# ProPrj_Videocraft_USB_Hub_2026-04-26.net
KiCad netlist of a schematic drawn in EasyEDA Pro
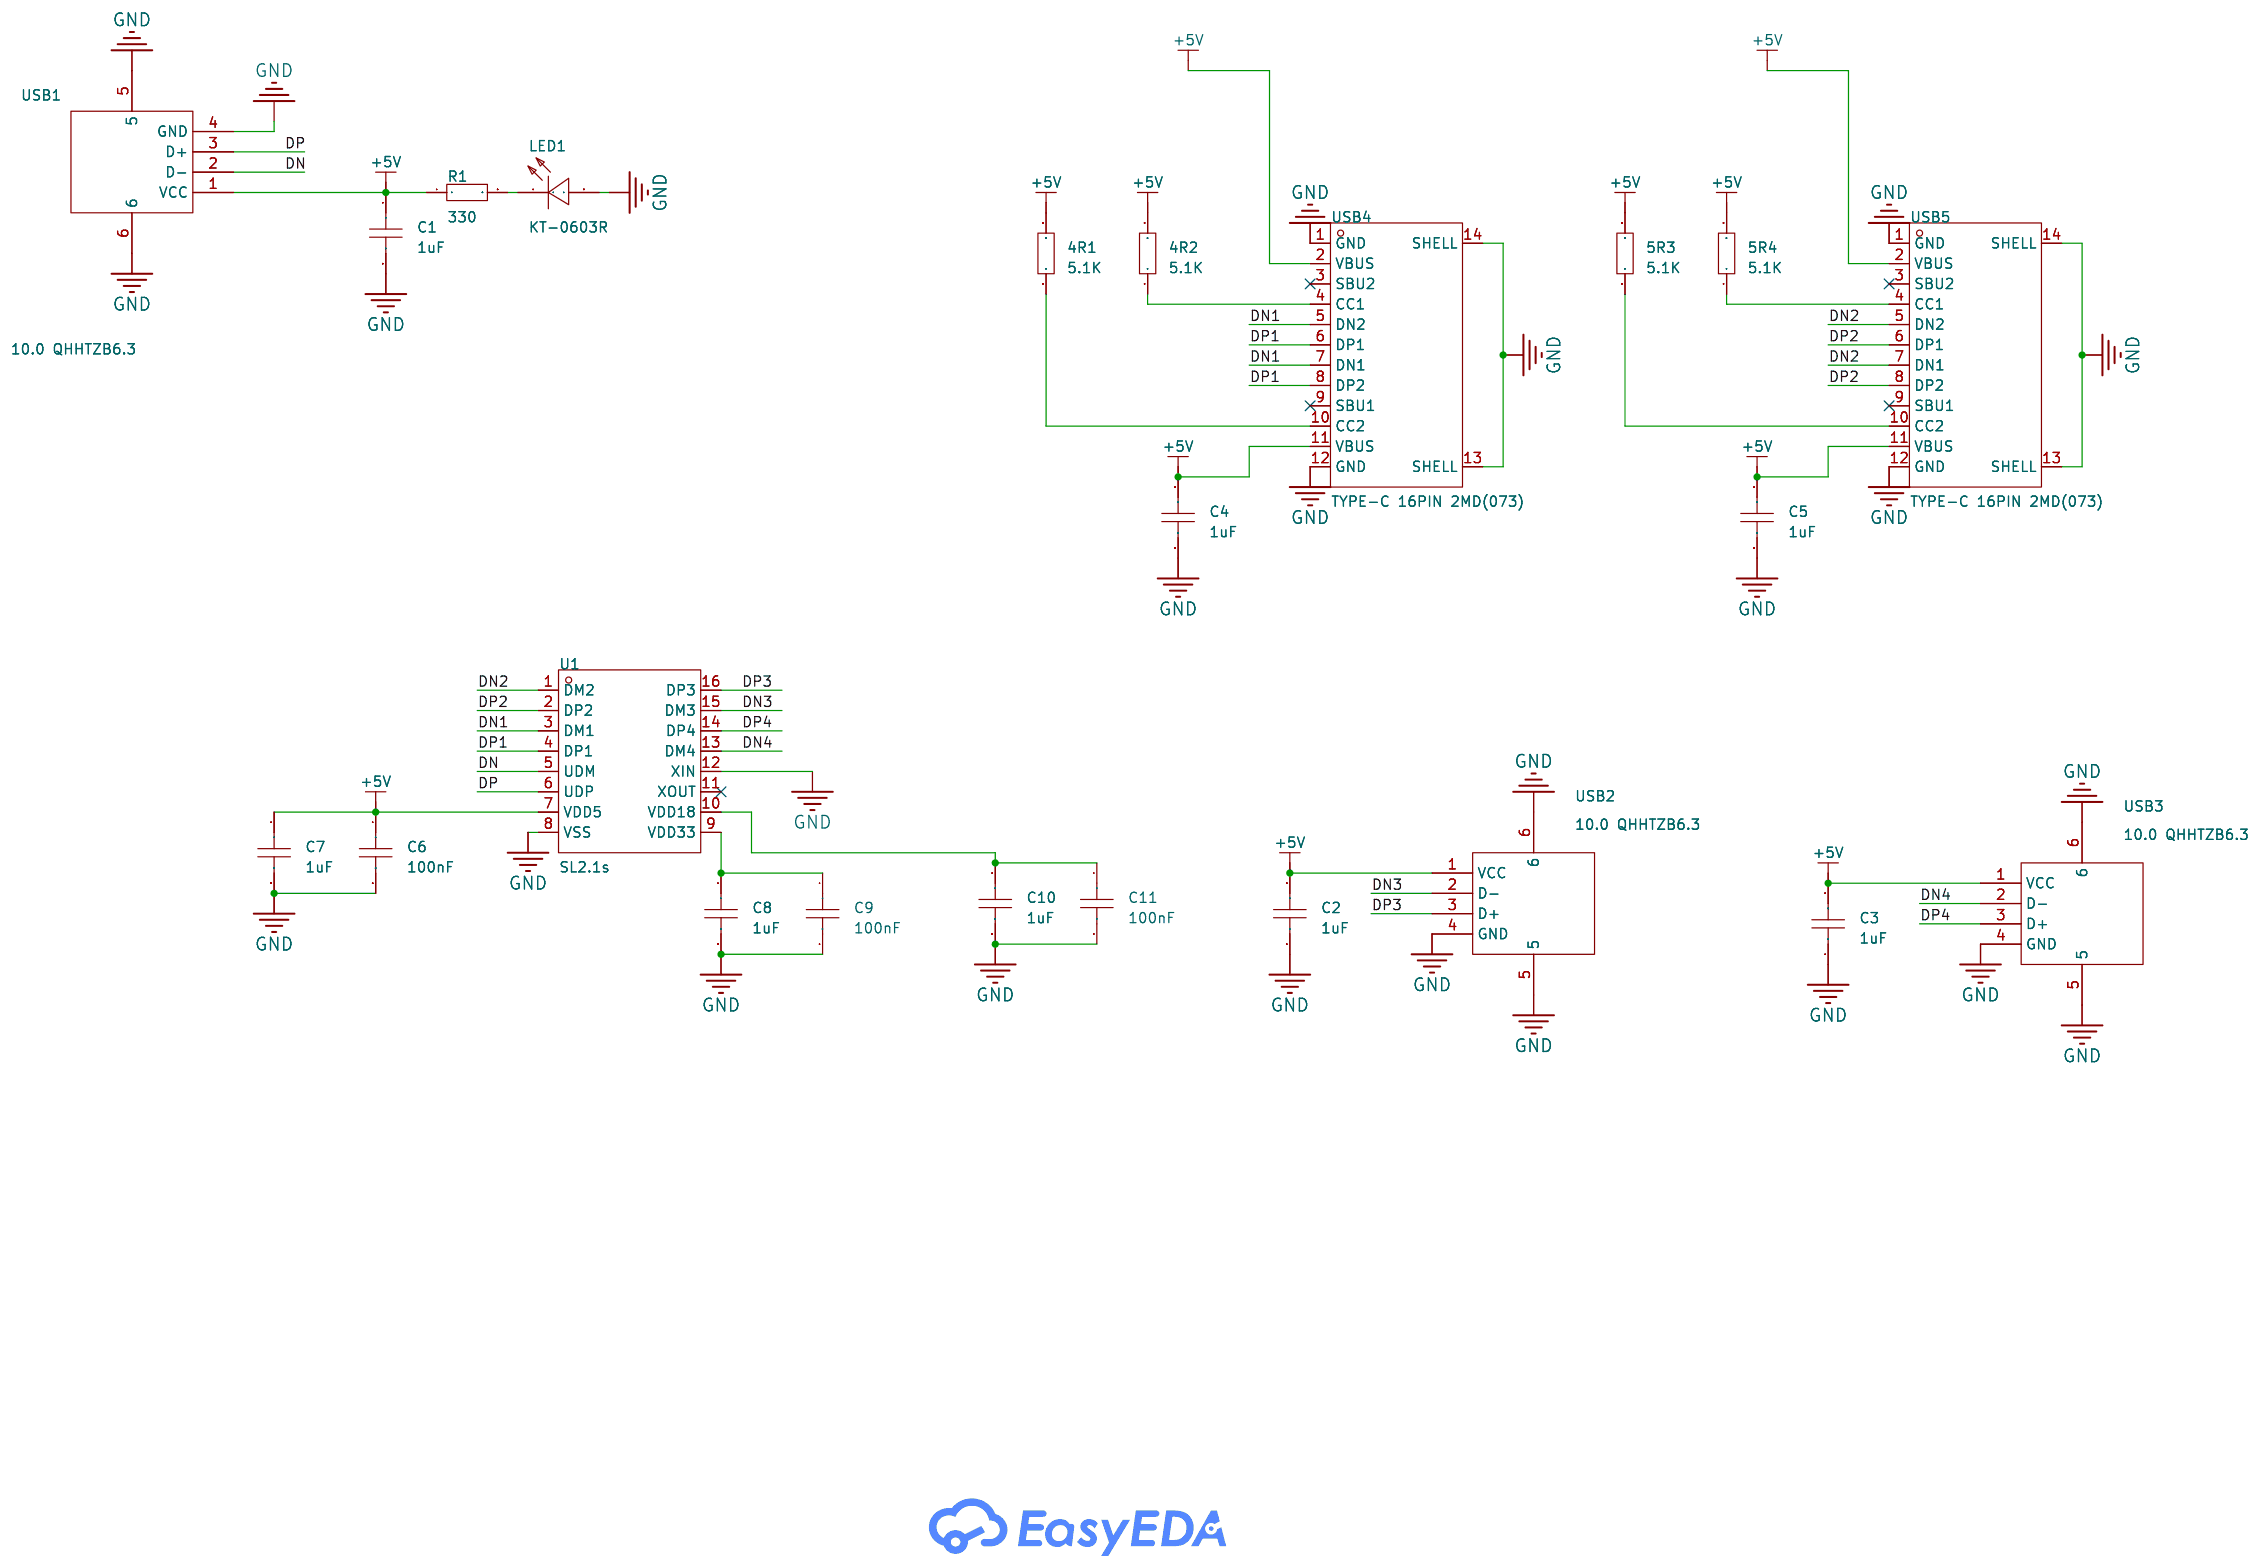
[diagram p0: schematic sheet]

(export (version "E")
  (design (tool "Eeschema 10.0.6"))
  (components
    (comp (ref "4R1")
      (value "5.1K")
      (footprint "easyedapro:R0603")
      (libsource (lib "easyedapro") (part "Res"))
    )
    (comp (ref "4R2")
      (value "5.1K")
      (footprint "easyedapro:R0603")
      (libsource (lib "easyedapro") (part "Res"))
    )
    (comp (ref "5R3")
      (value "5.1K")
      (footprint "easyedapro:R0603")
      (libsource (lib "easyedapro") (part "Res"))
    )
    (comp (ref "5R4")
      (value "5.1K")
      (footprint "easyedapro:R0603")
      (libsource (lib "easyedapro") (part "Res"))
    )
    (comp (ref "C1") (value "1uF") (footprint "easyedapro:C0603") (libsource (lib "easyedapro") (part "CAP")))
    (comp (ref "C2") (value "1uF") (footprint "easyedapro:C0603") (libsource (lib "easyedapro") (part "CAP")))
    (comp (ref "C3") (value "1uF") (footprint "easyedapro:C0603") (libsource (lib "easyedapro") (part "CAP")))
    (comp (ref "C4") (value "1uF") (footprint "easyedapro:C0603") (libsource (lib "easyedapro") (part "CAP")))
    (comp (ref "C5") (value "1uF") (footprint "easyedapro:C0603") (libsource (lib "easyedapro") (part "CAP")))
    (comp (ref "C6")
      (value "100nF")
      (footprint "easyedapro:C0603")
      (libsource (lib "easyedapro") (part "CAP"))
    )
    (comp (ref "C7") (value "1uF") (footprint "easyedapro:C0603") (libsource (lib "easyedapro") (part "CAP")))
    (comp (ref "C8") (value "1uF") (footprint "easyedapro:C0603") (libsource (lib "easyedapro") (part "CAP")))
    (comp (ref "C9")
      (value "100nF")
      (footprint "easyedapro:C0603")
      (libsource (lib "easyedapro") (part "CAP"))
    )
    (comp (ref "C10")
      (value "1uF")
      (footprint "easyedapro:C0603")
      (libsource (lib "easyedapro") (part "CAP"))
    )
    (comp (ref "C11")
      (value "100nF")
      (footprint "easyedapro:C0603")
      (libsource (lib "easyedapro") (part "CAP"))
    )
    (comp (ref "LED1")
      (value "KT-0603R")
      (footprint "easyedapro:LED0603-RD")
      (fields (field (name "Manufacturer") "KENTO"))
      (libsource (lib "easyedapro") (part "KT-0603R"))
    )
    (comp (ref "R1") (value "330") (footprint "easyedapro:R0603") (libsource (lib "easyedapro") (part "Res")))
    (comp (ref "U1")
      (value "SL2.1s")
      (footprint "easyedapro:SSOP-16_L4.6-W2.6-P0.53-LS4.0-BL")
      (fields (field (name "Manufacturer") "CoreChips(和芯润德)"))
      (libsource (lib "easyedapro") (part "SL2.1S"))
    )
    (comp (ref "USB1")
      (value "10.0 QHHTZB6.3")
      (footprint "easyedapro:USB-A-TH_10.0QHHTZB6.3")
      (fields (field (name "Manufacturer") "SHOU HAN(首韩)"))
      (libsource (lib "easyedapro") (part "10.0 QHHTZB6.3"))
    )
    (comp (ref "USB2")
      (value "10.0 QHHTZB6.3")
      (footprint "easyedapro:USB-A-TH_10.0QHHTZB6.3")
      (fields (field (name "Manufacturer") "SHOU HAN(首韩)"))
      (libsource (lib "easyedapro") (part "10.0 QHHTZB6.3"))
    )
    (comp (ref "USB3")
      (value "10.0 QHHTZB6.3")
      (footprint "easyedapro:USB-A-TH_10.0QHHTZB6.3")
      (fields (field (name "Manufacturer") "SHOU HAN(首韩)"))
      (libsource (lib "easyedapro") (part "10.0 QHHTZB6.3"))
    )
    (comp (ref "USB4")
      (value "TYPE-C 16PIN 2MD(073)")
      (footprint "easyedapro:USB-C-SMD_TYPE-C-6PIN-2MD-073")
      (fields (field (name "Manufacturer") "SHOU HAN(首韩)"))
      (libsource (lib "easyedapro") (part "TYPE-C 16PIN 2MD(073)"))
    )
    (comp (ref "USB5")
      (value "TYPE-C 16PIN 2MD(073)")
      (footprint "easyedapro:USB-C-SMD_TYPE-C-6PIN-2MD-073")
      (fields (field (name "Manufacturer") "SHOU HAN(首韩)"))
      (libsource (lib "easyedapro") (part "TYPE-C 16PIN 2MD(073)"))
    )
  )
  (nets
    (net (code "1") (name "+5V") (class "Default")
      (node (ref "4R1") (pin "2") (pinfunction "2_2") (pintype "input"))
      (node (ref "4R2") (pin "2") (pinfunction "2_2") (pintype "input"))
      (node (ref "5R3") (pin "2") (pinfunction "2_2") (pintype "input"))
      (node (ref "5R4") (pin "2") (pinfunction "2_2") (pintype "input"))
      (node (ref "C1") (pin "1") (pinfunction "1_1") (pintype "input"))
      (node (ref "C2") (pin "2") (pinfunction "2_2") (pintype "input"))
      (node (ref "C3") (pin "2") (pinfunction "2_2") (pintype "input"))
      (node (ref "C4") (pin "1") (pinfunction "1_1") (pintype "input"))
      (node (ref "C5") (pin "1") (pinfunction "1_1") (pintype "input"))
      (node (ref "C6") (pin "1") (pinfunction "1_1") (pintype "input"))
      (node (ref "C7") (pin "1") (pinfunction "1_1") (pintype "input"))
      (node (ref "R1") (pin "1") (pinfunction "1_1") (pintype "input"))
      (node (ref "U1") (pin "7") (pinfunction "VDD5_7") (pintype "unspecified"))
      (node (ref "USB1") (pin "1") (pinfunction "VCC_1") (pintype "unspecified"))
      (node (ref "USB2") (pin "1") (pinfunction "VCC_1") (pintype "unspecified"))
      (node (ref "USB3") (pin "1") (pinfunction "VCC_1") (pintype "unspecified"))
      (node (ref "USB4") (pin "11") (pinfunction "VBUS_11") (pintype "unspecified"))
      (node (ref "USB4") (pin "2") (pinfunction "VBUS_2") (pintype "unspecified"))
      (node (ref "USB5") (pin "11") (pinfunction "VBUS_11") (pintype "unspecified"))
      (node (ref "USB5") (pin "2") (pinfunction "VBUS_2") (pintype "unspecified"))
    )
    (net (code "2") (name "/DN") (class "Default")
      (node (ref "U1") (pin "5") (pinfunction "UDM_5") (pintype "unspecified"))
      (node (ref "USB1") (pin "2") (pinfunction "D-_2") (pintype "unspecified"))
    )
    (net (code "3") (name "/DN1") (class "Default")
      (node (ref "U1") (pin "3") (pinfunction "DM1_3") (pintype "unspecified"))
      (node (ref "USB4") (pin "5") (pinfunction "DN2_5") (pintype "unspecified"))
      (node (ref "USB4") (pin "7") (pinfunction "DN1_7") (pintype "unspecified"))
    )
    (net (code "4") (name "/DN2") (class "Default")
      (node (ref "U1") (pin "1") (pinfunction "DM2_1") (pintype "unspecified"))
      (node (ref "USB5") (pin "5") (pinfunction "DN2_5") (pintype "unspecified"))
      (node (ref "USB5") (pin "7") (pinfunction "DN1_7") (pintype "unspecified"))
    )
    (net (code "5") (name "/DN3") (class "Default")
      (node (ref "U1") (pin "15") (pinfunction "DM3_15") (pintype "unspecified"))
      (node (ref "USB2") (pin "2") (pinfunction "D-_2") (pintype "unspecified"))
    )
    (net (code "6") (name "/DN4") (class "Default")
      (node (ref "U1") (pin "13") (pinfunction "DM4_13") (pintype "unspecified"))
      (node (ref "USB3") (pin "2") (pinfunction "D-_2") (pintype "unspecified"))
    )
    (net (code "7") (name "/DP") (class "Default")
      (node (ref "U1") (pin "6") (pinfunction "UDP_6") (pintype "unspecified"))
      (node (ref "USB1") (pin "3") (pinfunction "D+_3") (pintype "unspecified"))
    )
    (net (code "8") (name "/DP1") (class "Default")
      (node (ref "U1") (pin "4") (pinfunction "DP1_4") (pintype "unspecified"))
      (node (ref "USB4") (pin "6") (pinfunction "DP1_6") (pintype "unspecified"))
      (node (ref "USB4") (pin "8") (pinfunction "DP2_8") (pintype "unspecified"))
    )
    (net (code "9") (name "/DP2") (class "Default")
      (node (ref "U1") (pin "2") (pinfunction "DP2_2") (pintype "unspecified"))
      (node (ref "USB5") (pin "6") (pinfunction "DP1_6") (pintype "unspecified"))
      (node (ref "USB5") (pin "8") (pinfunction "DP2_8") (pintype "unspecified"))
    )
    (net (code "10") (name "/DP3") (class "Default")
      (node (ref "U1") (pin "16") (pinfunction "DP3_16") (pintype "unspecified"))
      (node (ref "USB2") (pin "3") (pinfunction "D+_3") (pintype "unspecified"))
    )
    (net (code "11") (name "/DP4") (class "Default")
      (node (ref "U1") (pin "14") (pinfunction "DP4_14") (pintype "unspecified"))
      (node (ref "USB3") (pin "3") (pinfunction "D+_3") (pintype "unspecified"))
    )
    (net (code "12") (name "GND") (class "Default")
      (node (ref "C1") (pin "2") (pinfunction "2_2") (pintype "input"))
      (node (ref "C10") (pin "2") (pinfunction "2_2") (pintype "input"))
      (node (ref "C11") (pin "2") (pinfunction "2_2") (pintype "input"))
      (node (ref "C2") (pin "1") (pinfunction "1_1") (pintype "input"))
      (node (ref "C3") (pin "1") (pinfunction "1_1") (pintype "input"))
      (node (ref "C4") (pin "2") (pinfunction "2_2") (pintype "input"))
      (node (ref "C5") (pin "2") (pinfunction "2_2") (pintype "input"))
      (node (ref "C6") (pin "2") (pinfunction "2_2") (pintype "input"))
      (node (ref "C7") (pin "2") (pinfunction "2_2") (pintype "input"))
      (node (ref "C8") (pin "2") (pinfunction "2_2") (pintype "input"))
      (node (ref "C9") (pin "2") (pinfunction "2_2") (pintype "input"))
      (node (ref "LED1") (pin "2") (pinfunction "A_2") (pintype "unspecified"))
      (node (ref "U1") (pin "12") (pinfunction "XIN_12") (pintype "unspecified"))
      (node (ref "U1") (pin "8") (pinfunction "VSS_8") (pintype "unspecified"))
      (node (ref "USB1") (pin "4") (pinfunction "GND_4") (pintype "unspecified"))
      (node (ref "USB1") (pin "5") (pinfunction "5_5") (pintype "unspecified"))
      (node (ref "USB1") (pin "6") (pinfunction "6_6") (pintype "unspecified"))
      (node (ref "USB2") (pin "4") (pinfunction "GND_4") (pintype "unspecified"))
      (node (ref "USB2") (pin "5") (pinfunction "5_5") (pintype "unspecified"))
      (node (ref "USB2") (pin "6") (pinfunction "6_6") (pintype "unspecified"))
      (node (ref "USB3") (pin "4") (pinfunction "GND_4") (pintype "unspecified"))
      (node (ref "USB3") (pin "5") (pinfunction "5_5") (pintype "unspecified"))
      (node (ref "USB3") (pin "6") (pinfunction "6_6") (pintype "unspecified"))
      (node (ref "USB4") (pin "1") (pinfunction "GND_1") (pintype "unspecified"))
      (node (ref "USB4") (pin "12") (pinfunction "GND_12") (pintype "unspecified"))
      (node (ref "USB4") (pin "13") (pinfunction "SHELL_13") (pintype "unspecified"))
      (node (ref "USB4") (pin "14") (pinfunction "SHELL_14") (pintype "unspecified"))
      (node (ref "USB5") (pin "1") (pinfunction "GND_1") (pintype "unspecified"))
      (node (ref "USB5") (pin "12") (pinfunction "GND_12") (pintype "unspecified"))
      (node (ref "USB5") (pin "13") (pinfunction "SHELL_13") (pintype "unspecified"))
      (node (ref "USB5") (pin "14") (pinfunction "SHELL_14") (pintype "unspecified"))
    )
    (net (code "13") (name "Net-(LED1-K)") (class "Default")
      (node (ref "LED1") (pin "1") (pinfunction "K_1") (pintype "unspecified"))
      (node (ref "R1") (pin "2") (pinfunction "2_2") (pintype "input"))
    )
    (net (code "14") (name "Net-(U1-VDD18)") (class "Default")
      (node (ref "C10") (pin "1") (pinfunction "1_1") (pintype "input"))
      (node (ref "C11") (pin "1") (pinfunction "1_1") (pintype "input"))
      (node (ref "U1") (pin "10") (pinfunction "VDD18_10") (pintype "unspecified"))
    )
    (net (code "15") (name "Net-(U1-VDD33)") (class "Default")
      (node (ref "C8") (pin "1") (pinfunction "1_1") (pintype "input"))
      (node (ref "C9") (pin "1") (pinfunction "1_1") (pintype "input"))
      (node (ref "U1") (pin "9") (pinfunction "VDD33_9") (pintype "unspecified"))
    )
    (net (code "16") (name "Net-(USB4-CC1)") (class "Default")
      (node (ref "4R2") (pin "1") (pinfunction "1_1") (pintype "input"))
      (node (ref "USB4") (pin "4") (pinfunction "CC1_4") (pintype "unspecified"))
    )
    (net (code "17") (name "Net-(USB4-CC2)") (class "Default")
      (node (ref "4R1") (pin "1") (pinfunction "1_1") (pintype "input"))
      (node (ref "USB4") (pin "10") (pinfunction "CC2_10") (pintype "unspecified"))
    )
    (net (code "18") (name "Net-(USB5-CC1)") (class "Default")
      (node (ref "5R4") (pin "1") (pinfunction "1_1") (pintype "input"))
      (node (ref "USB5") (pin "4") (pinfunction "CC1_4") (pintype "unspecified"))
    )
    (net (code "19") (name "Net-(USB5-CC2)") (class "Default")
      (node (ref "5R3") (pin "1") (pinfunction "1_1") (pintype "input"))
      (node (ref "USB5") (pin "10") (pinfunction "CC2_10") (pintype "unspecified"))
    )
    (net (code "20") (name "unconnected-(U1-XOUT-Pad11)") (class "Default")
      (node (ref "U1") (pin "11") (pinfunction "XOUT_11") (pintype "unspecified+no_connect"))
    )
    (net (code "21") (name "unconnected-(USB4-SBU1-Pad9)") (class "Default")
      (node (ref "USB4") (pin "9") (pinfunction "SBU1_9") (pintype "unspecified+no_connect"))
    )
    (net (code "22") (name "unconnected-(USB4-SBU2-Pad3)") (class "Default")
      (node (ref "USB4") (pin "3") (pinfunction "SBU2_3") (pintype "unspecified+no_connect"))
    )
    (net (code "23") (name "unconnected-(USB5-SBU1-Pad9)") (class "Default")
      (node (ref "USB5") (pin "9") (pinfunction "SBU1_9") (pintype "unspecified+no_connect"))
    )
    (net (code "24") (name "unconnected-(USB5-SBU2-Pad3)") (class "Default")
      (node (ref "USB5") (pin "3") (pinfunction "SBU2_3") (pintype "unspecified+no_connect"))
    )
  )
)
